# Adafruit_Hallowing_M0_Express.net
KiCad netlist of a schematic drawn in EAGLE
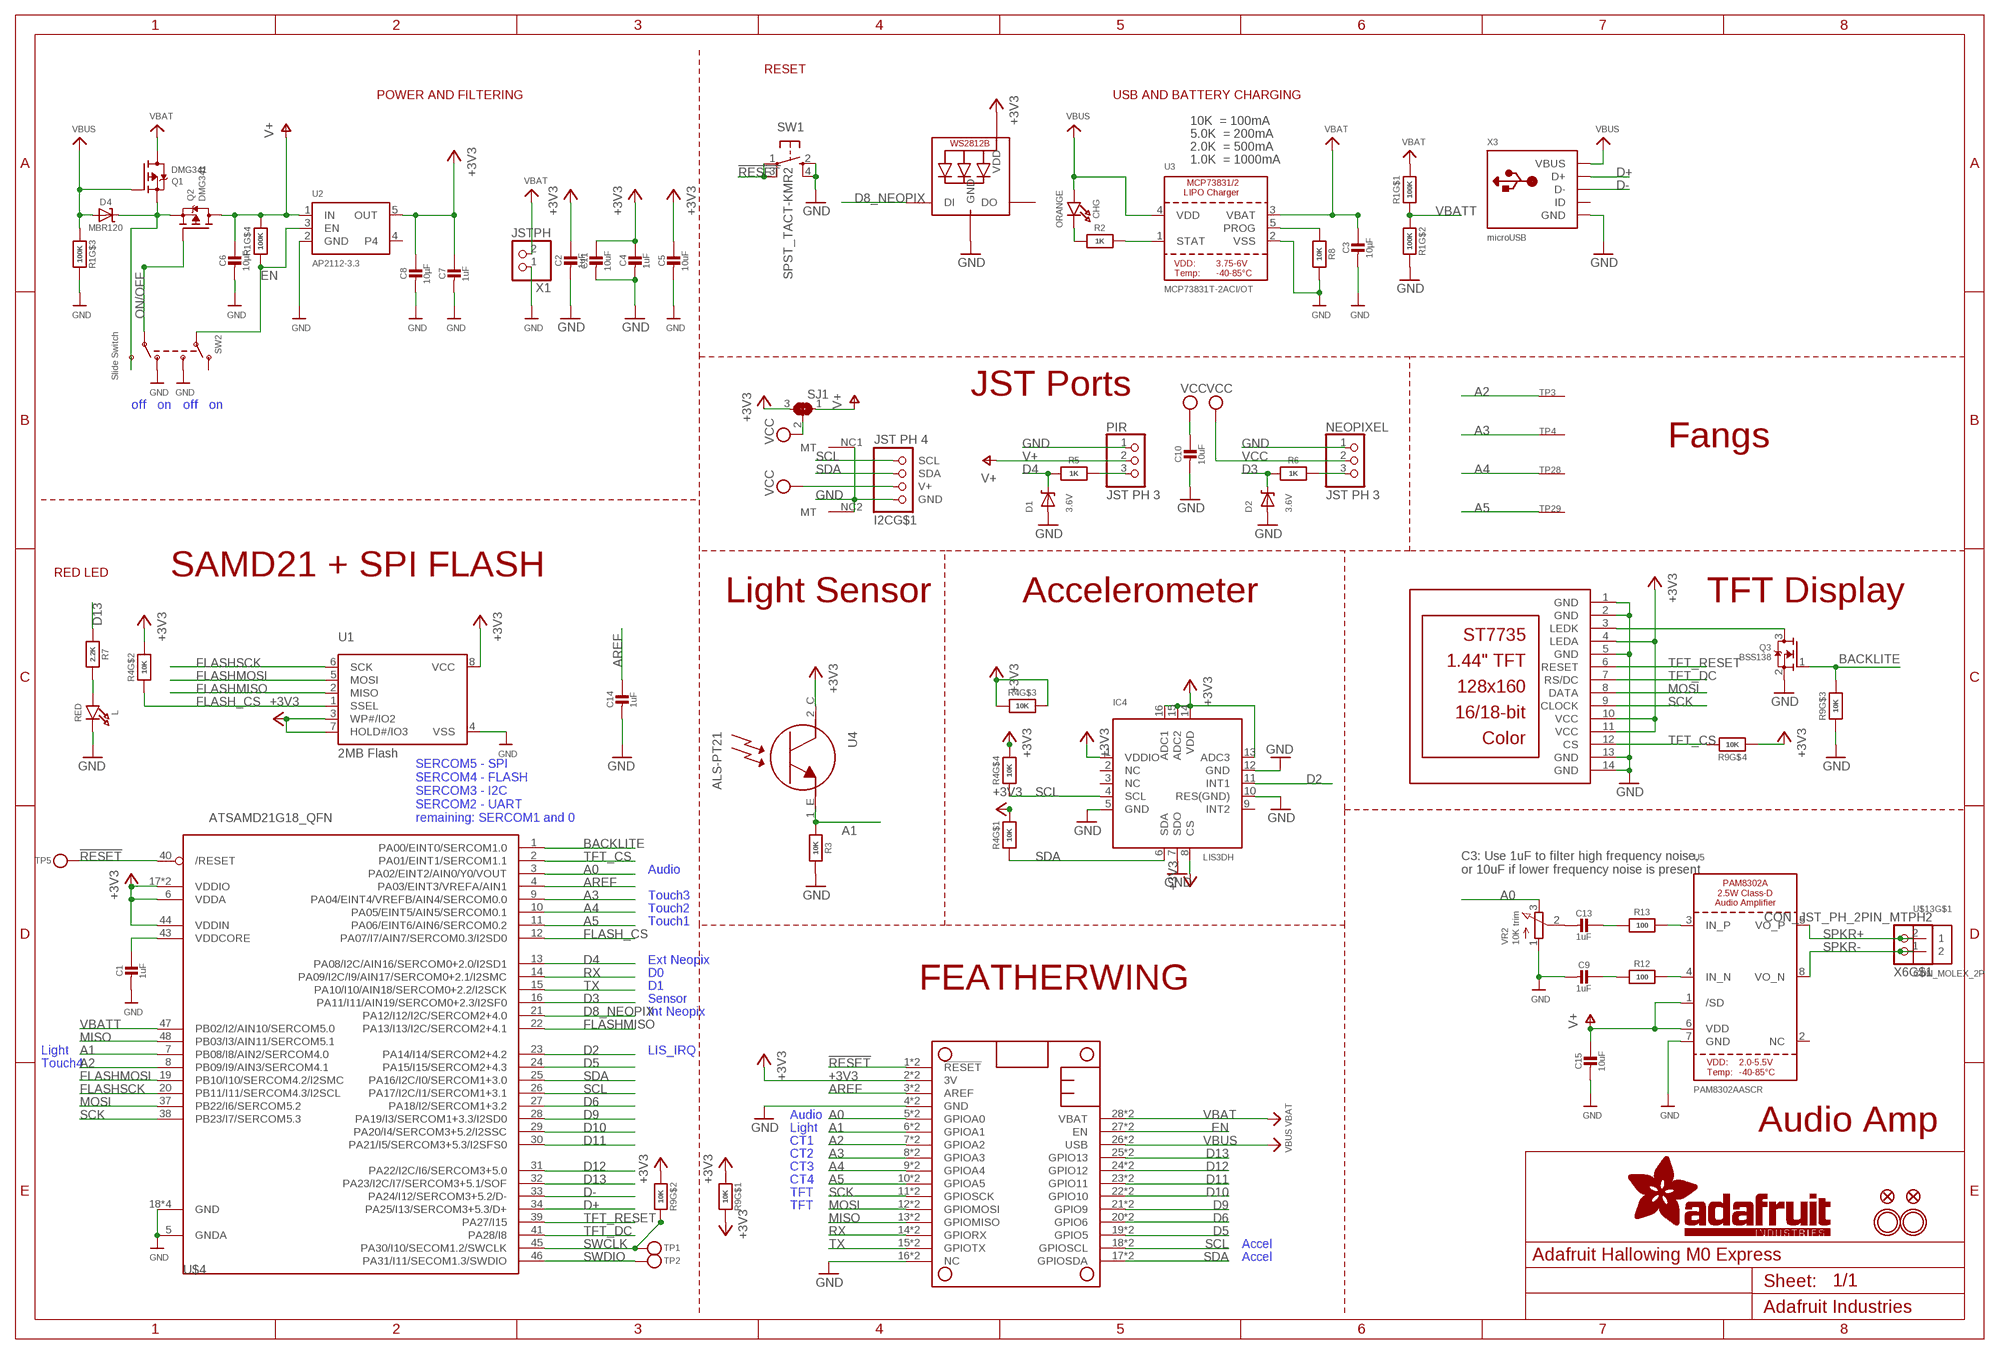
[diagram p0: schematic, sheet 1]

(export (version "E")
  (design (tool "Eeschema 10.0.6"))
  (components
    (comp (ref "C1")
      (value "1uF")
      (footprint "eagle-import:0603-NO")
      (libsource (lib "eagle-import") (part "CAP_CERAMIC0603_NO"))
    )
    (comp (ref "C2")
      (value "1uF")
      (footprint "eagle-import:0603-NO")
      (libsource (lib "eagle-import") (part "CAP_CERAMIC0603_NO"))
    )
    (comp (ref "C3")
      (value "10µF")
      (footprint "eagle-import:0805-NO")
      (libsource (lib "eagle-import") (part "CAP_CERAMIC0805-NOOUTLINE"))
    )
    (comp (ref "C4")
      (value "1uF")
      (footprint "eagle-import:0603-NO")
      (libsource (lib "eagle-import") (part "CAP_CERAMIC0603_NO"))
    )
    (comp (ref "C5")
      (value "10uF")
      (footprint "eagle-import:0805-NO")
      (libsource (lib "eagle-import") (part "CAP_CERAMIC0805-NOOUTLINE"))
    )
    (comp (ref "C6")
      (value "10µF")
      (footprint "eagle-import:0805-NO")
      (libsource (lib "eagle-import") (part "CAP_CERAMIC0805-NOOUTLINE"))
    )
    (comp (ref "C7")
      (value "1uF")
      (footprint "eagle-import:0603-NO")
      (libsource (lib "eagle-import") (part "CAP_CERAMIC0603_NO"))
    )
    (comp (ref "C8")
      (value "10µF")
      (footprint "eagle-import:0805_10MGAP")
      (libsource (lib "eagle-import") (part "CAP_CERAMIC0805_10MGAP"))
    )
    (comp (ref "C9")
      (value "1uF")
      (footprint "eagle-import:0603-NO")
      (libsource (lib "eagle-import") (part "CAP_CERAMIC0603_NO"))
    )
    (comp (ref "C10")
      (value "10uF")
      (footprint "eagle-import:0805-NO")
      (libsource (lib "eagle-import") (part "CAP_CERAMIC0805-NOOUTLINE"))
    )
    (comp (ref "C11")
      (value "10uF")
      (footprint "eagle-import:0805_10MGAP")
      (libsource (lib "eagle-import") (part "CAP_CERAMIC0805_10MGAP"))
    )
    (comp (ref "C13")
      (value "1uF")
      (footprint "eagle-import:0603-NO")
      (libsource (lib "eagle-import") (part "CAP_CERAMIC0603_NO"))
    )
    (comp (ref "C14")
      (value "1uF")
      (footprint "eagle-import:0603-NO")
      (libsource (lib "eagle-import") (part "CAP_CERAMIC0603_NO"))
    )
    (comp (ref "C15")
      (value "10uF")
      (footprint "eagle-import:0805-NO")
      (libsource (lib "eagle-import") (part "CAP_CERAMIC0805-NOOUTLINE"))
    )
    (comp (ref "CHG")
      (value "ORANGE")
      (footprint "eagle-import:CHIPLED_0805_NOOUTLINE")
      (libsource (lib "eagle-import") (part "LED0805_NOOUTLINE"))
    )
    (comp (ref "D1")
      (value "3.6V")
      (footprint "eagle-import:SOD-323")
      (libsource (lib "eagle-import") (part "DIODE-ZENERSOD323"))
    )
    (comp (ref "D2")
      (value "3.6V")
      (footprint "eagle-import:SOD-323")
      (libsource (lib "eagle-import") (part "DIODE-ZENERSOD323"))
    )
    (comp (ref "D4")
      (value "MBR120")
      (footprint "eagle-import:SOD-123")
      (libsource (lib "eagle-import") (part "DIODE-SCHOTTKYSOD-123"))
    )
    (comp (ref "I2C")
      (value "JST PH 4")
      (footprint "eagle-import:JSTPH4")
      (libsource (lib "eagle-import") (part "STEMMA_I2C_RASMT"))
    )
    (comp (ref "IC4")
      (value "LIS3DH")
      (footprint "eagle-import:LGA16_3X3MM")
      (libsource (lib "eagle-import") (part "ACCEL_LIS3DHTR"))
    )
    (comp (ref "L")
      (value "RED")
      (footprint "eagle-import:CHIPLED_0805_NOOUTLINE")
      (libsource (lib "eagle-import") (part "LED0805_NOOUTLINE"))
    )
    (comp (ref "LED1")
      (value "WS2812B3535")
      (footprint "eagle-import:LED3535")
      (libsource (lib "eagle-import") (part "WS2812B3535"))
    )
    (comp (ref "MS1")
      (value "FEATHERWING_SMTDUALNOHOLES")
      (footprint "eagle-import:FEATHERWING_SMT_NOHOLES")
      (libsource (lib "eagle-import") (part "FEATHERWING_SMTDUALNOHOLES"))
    )
    (comp (ref "NEOPIXEL")
      (value "JST PH 3")
      (footprint "eagle-import:JSTPH3")
      (libsource (lib "eagle-import") (part "CON_JST_PH_3PIN"))
    )
    (comp (ref "PIR")
      (value "JST PH 3")
      (footprint "eagle-import:JSTPH3")
      (libsource (lib "eagle-import") (part "CON_JST_PH_3PIN"))
    )
    (comp (ref "Q1")
      (value "DMG341")
      (footprint "eagle-import:SOT23-R")
      (libsource (lib "eagle-import") (part "MOSFET-P"))
    )
    (comp (ref "Q2")
      (value "DMG341")
      (footprint "eagle-import:SOT23-R")
      (libsource (lib "eagle-import") (part "MOSFET-P"))
    )
    (comp (ref "Q3")
      (value "BSS138")
      (footprint "eagle-import:SOT23-WIDE")
      (libsource (lib "eagle-import") (part "MOSFET-NWIDE"))
    )
    (comp (ref "R1")
      (value "100K")
      (footprint "eagle-import:RESPACK_4X0603")
      (libsource (lib "eagle-import") (part "RESISTOR_4PACK"))
    )
    (comp (ref "R2")
      (value "1K")
      (footprint "eagle-import:0603-NO")
      (libsource (lib "eagle-import") (part "RESISTOR_0603_NOOUT"))
    )
    (comp (ref "R3")
      (value "10K")
      (footprint "eagle-import:0603-NO")
      (libsource (lib "eagle-import") (part "RESISTOR_0603_NOOUT"))
    )
    (comp (ref "R4")
      (value "10K")
      (footprint "eagle-import:RESPACK_4X0603")
      (libsource (lib "eagle-import") (part "RESISTOR_4PACK"))
    )
    (comp (ref "R5")
      (value "1K")
      (footprint "eagle-import:0603-NO")
      (libsource (lib "eagle-import") (part "RESISTOR_0603_NOOUT"))
    )
    (comp (ref "R6")
      (value "1K")
      (footprint "eagle-import:0603-NO")
      (libsource (lib "eagle-import") (part "RESISTOR_0603_NOOUT"))
    )
    (comp (ref "R7")
      (value "2.2K")
      (footprint "eagle-import:0603-NO")
      (libsource (lib "eagle-import") (part "RESISTOR_0603_NOOUT"))
    )
    (comp (ref "R8")
      (value "10K")
      (footprint "eagle-import:0603-NO")
      (libsource (lib "eagle-import") (part "RESISTOR_0603_NOOUT"))
    )
    (comp (ref "R9")
      (value "10K")
      (footprint "eagle-import:RESPACK_4X0603")
      (libsource (lib "eagle-import") (part "RESISTOR_4PACK"))
    )
    (comp (ref "R12")
      (value "100")
      (footprint "eagle-import:0603-NO")
      (libsource (lib "eagle-import") (part "RESISTOR_0603_NOOUT"))
    )
    (comp (ref "R13")
      (value "100")
      (footprint "eagle-import:0603-NO")
      (libsource (lib "eagle-import") (part "RESISTOR_0603_NOOUT"))
    )
    (comp (ref "SJ1")
      (value "SOLDERJUMPER_2WAY")
      (footprint "eagle-import:SOLDERJUMPER_2WAY_OPEN_NOPASTE")
      (libsource (lib "eagle-import") (part "SOLDERJUMPER_2WAY"))
    )
    (comp (ref "SW1")
      (value "SPST_TACT-KMR2")
      (footprint "eagle-import:KMR2")
      (libsource (lib "eagle-import") (part "SPST_TACT-KMR2"))
    )
    (comp (ref "SW2")
      (value "Slide Switch")
      (footprint "eagle-import:EG1390")
      (libsource (lib "eagle-import") (part "SWITCH_DPDTEG1390"))
    )
    (comp (ref "TFT")
      (value "DISP_LCD_ST7735_1.44IN")
      (footprint "eagle-import:TFT_1.44IN_128_128")
      (libsource (lib "eagle-import") (part "DISP_LCD_ST7735_1.44IN"))
    )
    (comp (ref "TP1")
      (value "TESTPOINTROUND1.5MM")
      (footprint "eagle-import:TESTPOINT_ROUND_1.5MM")
      (libsource (lib "eagle-import") (part "TESTPOINTROUND1.5MM"))
    )
    (comp (ref "TP2")
      (value "TESTPOINTROUND1.5MM")
      (footprint "eagle-import:TESTPOINT_ROUND_1.5MM")
      (libsource (lib "eagle-import") (part "TESTPOINTROUND1.5MM"))
    )
    (comp (ref "TP3")
      (value "SEWTAP_ALLILONG")
      (footprint "eagle-import:PCB_ALLI_LONG")
      (libsource (lib "eagle-import") (part "SEWTAP_ALLILONG"))
    )
    (comp (ref "TP4")
      (value "SEWTAPPCB_ALLIGATOR")
      (footprint "eagle-import:PCB_ALLI")
      (libsource (lib "eagle-import") (part "SEWTAPPCB_ALLIGATOR"))
    )
    (comp (ref "TP5")
      (value "TESTPOINTROUND1.5MM")
      (footprint "eagle-import:TESTPOINT_ROUND_1.5MM")
      (libsource (lib "eagle-import") (part "TESTPOINTROUND1.5MM"))
    )
    (comp (ref "TP28")
      (value "SEWTAPPCB_ALLIGATOR")
      (footprint "eagle-import:PCB_ALLI")
      (libsource (lib "eagle-import") (part "SEWTAPPCB_ALLIGATOR"))
    )
    (comp (ref "TP29")
      (value "SEWTAP_ALLILONG")
      (footprint "eagle-import:PCB_ALLI_LONG")
      (libsource (lib "eagle-import") (part "SEWTAP_ALLILONG"))
    )
    (comp (ref "U$4")
      (value "ATSAMD21G18_QFN")
      (footprint "eagle-import:TQFN48_7MM")
      (libsource (lib "eagle-import") (part "ATSAMD21G_QFN"))
    )
    (comp (ref "U$13")
      (value "CON_MOLEX_2P")
      (footprint "eagle-import:53398-0271")
      (libsource (lib "eagle-import") (part "CON_MOLEX_2P"))
    )
    (comp (ref "U$31")
      (value "MOUNTINGHOLE2.5")
      (footprint "eagle-import:MOUNTINGHOLE_2.5_PLATED")
      (libsource (lib "eagle-import") (part "MOUNTINGHOLE2.5"))
    )
    (comp (ref "U$32")
      (value "MOUNTINGHOLE2.5")
      (footprint "eagle-import:MOUNTINGHOLE_2.5_PLATED")
      (libsource (lib "eagle-import") (part "MOUNTINGHOLE2.5"))
    )
    (comp (ref "U$34")
      (value "FIDUCIAL_1MM")
      (footprint "eagle-import:FIDUCIAL_1MM")
      (libsource (lib "eagle-import") (part "FIDUCIAL_1MM"))
    )
    (comp (ref "U$35")
      (value "FIDUCIAL_1MM")
      (footprint "eagle-import:FIDUCIAL_1MM")
      (libsource (lib "eagle-import") (part "FIDUCIAL_1MM"))
    )
    (comp (ref "U1")
      (value "2MB Flash")
      (footprint "eagle-import:SOIC8_208MIL")
      (libsource (lib "eagle-import") (part "SPIFLASH_8PIN208MIL"))
    )
    (comp (ref "U2")
      (value "AP2112-3.3")
      (footprint "eagle-import:SOT23-5")
      (libsource (lib "eagle-import") (part "VREG_SOT23-5"))
    )
    (comp (ref "U3")
      (value "MCP73831T-2ACI/OT")
      (footprint "eagle-import:SOT23-5")
      (libsource (lib "eagle-import") (part "MCP73831/2"))
    )
    (comp (ref "U4")
      (value "ALS-PT21")
      (footprint "eagle-import:ALS-PT26-21C")
      (libsource (lib "eagle-import") (part "PHOTOTRANSISTOR_PT26-21C"))
    )
    (comp (ref "U5")
      (value "PAM8302AASCR")
      (footprint "eagle-import:MSOP8_0.65MM")
      (libsource (lib "eagle-import") (part "AUDIOAMP_PAM8302A"))
    )
    (comp (ref "VR2")
      (value "10K trim")
      (footprint "eagle-import:TRIMPOT_BOURNS_3303W")
      (libsource (lib "eagle-import") (part "TRIMPOT3303W/X"))
    )
    (comp (ref "X1")
      (value "JSTPH")
      (footprint "eagle-import:JSTPH2")
      (libsource (lib "eagle-import") (part "CON_JST_PH_2PIN"))
    )
    (comp (ref "X3")
      (value "microUSB")
      (footprint "eagle-import:4UCONN_20329_V2")
      (libsource (lib "eagle-import") (part "USB_MICRO_20329_V2"))
    )
    (comp (ref "X6")
      (value "CON_JST_PH_2PIN_MTPH2")
      (footprint "eagle-import:JSTPH2")
      (libsource (lib "eagle-import") (part "CON_JST_PH_2PIN_MTPH2"))
    )
  )
  (nets
    (net (code "1") (name "+3V3") (class "Default")
      (node (ref "C11") (pin "1") (pinfunction "1_1") (pintype "passive"))
      (node (ref "C2") (pin "1") (pinfunction "1_1") (pintype "passive"))
      (node (ref "C4") (pin "1") (pinfunction "1_1") (pintype "passive"))
      (node (ref "C5") (pin "1") (pinfunction "1_1") (pintype "passive"))
      (node (ref "C7") (pin "1") (pinfunction "1_1") (pintype "passive"))
      (node (ref "C8") (pin "1") (pinfunction "1_1") (pintype "passive"))
      (node (ref "IC4") (pin "1") (pinfunction "VDDIO_1") (pintype "power_in"))
      (node (ref "IC4") (pin "13") (pinfunction "ADC3_13") (pintype "input"))
      (node (ref "IC4") (pin "14") (pinfunction "VDD_14") (pintype "power_in"))
      (node (ref "IC4") (pin "15") (pinfunction "ADC2_15") (pintype "input"))
      (node (ref "IC4") (pin "16") (pinfunction "ADC1_16") (pintype "input"))
      (node (ref "IC4") (pin "8") (pinfunction "CS_8") (pintype "input"))
      (node (ref "LED1") (pin "2") (pinfunction "VDD_2") (pintype "power_in"))
      (node (ref "MS1") (pin "2") (pinfunction "3V_2") (pintype "power_in"))
      (node (ref "MS1") (pin "2'") (pinfunction "3V_2'") (pintype "power_in"))
      (node (ref "R4") (pin "3") (pinfunction "1_3") (pintype "passive"))
      (node (ref "R4") (pin "5") (pinfunction "2_5") (pintype "passive"))
      (node (ref "R4") (pin "6") (pinfunction "2_6") (pintype "passive"))
      (node (ref "R4") (pin "7") (pinfunction "2_7") (pintype "passive"))
      (node (ref "R4") (pin "8") (pinfunction "2_8") (pintype "passive"))
      (node (ref "R9") (pin "1") (pinfunction "1_1") (pintype "passive"))
      (node (ref "R9") (pin "2") (pinfunction "1_2") (pintype "passive"))
      (node (ref "R9") (pin "4") (pinfunction "1_4") (pintype "passive"))
      (node (ref "R9") (pin "8") (pinfunction "2_8") (pintype "passive"))
      (node (ref "SJ1") (pin "3") (pinfunction "3_3") (pintype "passive"))
      (node (ref "TFT") (pin "10") (pinfunction "VCC_10") (pintype "power_in"))
      (node (ref "TFT") (pin "11") (pinfunction "VCC_11") (pintype "power_in"))
      (node (ref "TFT") (pin "4") (pinfunction "LEDA_4") (pintype "input"))
      (node (ref "U$4") (pin "17") (pinfunction "VDDIO_17") (pintype "power_in"))
      (node (ref "U$4") (pin "36") (pinfunction "VDDIO_36") (pintype "power_in"))
      (node (ref "U$4") (pin "44") (pinfunction "VDDIN_44") (pintype "power_in"))
      (node (ref "U$4") (pin "6") (pinfunction "VDDA_6") (pintype "power_in"))
      (node (ref "U1") (pin "3") (pinfunction "WP#/IO2_3") (pintype "bidirectional"))
      (node (ref "U1") (pin "7") (pinfunction "HOLD#/IO3_7") (pintype "bidirectional"))
      (node (ref "U1") (pin "8") (pinfunction "VCC_8") (pintype "bidirectional"))
      (node (ref "U2") (pin "5") (pinfunction "OUT_5") (pintype "power_in"))
      (node (ref "U4") (pin "2_C") (pinfunction "C_2_C") (pintype "bidirectional"))
    )
    (net (code "2") (name "/A0") (class "Default")
      (node (ref "MS1") (pin "5") (pinfunction "GPIOA0_5") (pintype "bidirectional"))
      (node (ref "MS1") (pin "5'") (pinfunction "GPIOA0_5'") (pintype "bidirectional"))
      (node (ref "U$4") (pin "3") (pinfunction "PA02/EINT2/AIN0/Y0/VOUT_3") (pintype "bidirectional"))
      (node (ref "VR2") (pin "3") (pinfunction "E_3") (pintype "passive"))
    )
    (net (code "3") (name "/A1") (class "Default")
      (node (ref "MS1") (pin "6") (pinfunction "GPIOA1_6") (pintype "bidirectional"))
      (node (ref "MS1") (pin "6'") (pinfunction "GPIOA1_6'") (pintype "bidirectional"))
      (node (ref "R3") (pin "2") (pinfunction "2_2") (pintype "passive"))
      (node (ref "U$4") (pin "7") (pinfunction "PB08/I8/AIN2/SERCOM4.0_7") (pintype "bidirectional"))
      (node (ref "U4") (pin "1_E") (pinfunction "E_1_E") (pintype "bidirectional"))
    )
    (net (code "4") (name "/A2") (class "Default")
      (node (ref "MS1") (pin "7") (pinfunction "GPIOA2_7") (pintype "bidirectional"))
      (node (ref "MS1") (pin "7'") (pinfunction "GPIOA2_7'") (pintype "bidirectional"))
      (node (ref "TP3") (pin "P$1") (pinfunction "SEW_P$1") (pintype "bidirectional"))
      (node (ref "U$4") (pin "8") (pinfunction "PB09/I9/AIN3/SERCOM4.1_8") (pintype "bidirectional"))
    )
    (net (code "5") (name "/A3") (class "Default")
      (node (ref "MS1") (pin "8") (pinfunction "GPIOA3_8") (pintype "bidirectional"))
      (node (ref "MS1") (pin "8'") (pinfunction "GPIOA3_8'") (pintype "bidirectional"))
      (node (ref "TP4") (pin "P$1") (pinfunction "SEW_P$1") (pintype "bidirectional"))
      (node (ref "U$4") (pin "9") (pinfunction "PA04/EINT4/VREFB/AIN4/SERCOM0.0_9") (pintype "bidirectional"))
    )
    (net (code "6") (name "/A4") (class "Default")
      (node (ref "MS1") (pin "9") (pinfunction "GPIOA4_9") (pintype "bidirectional"))
      (node (ref "MS1") (pin "9'") (pinfunction "GPIOA4_9'") (pintype "bidirectional"))
      (node (ref "TP28") (pin "P$1") (pinfunction "SEW_P$1") (pintype "bidirectional"))
      (node (ref "U$4") (pin "10") (pinfunction "PA05/EINT5/AIN5/SERCOM0.1_10") (pintype "bidirectional"))
    )
    (net (code "7") (name "/A5") (class "Default")
      (node (ref "MS1") (pin "10") (pinfunction "GPIOA5_10") (pintype "bidirectional"))
      (node (ref "MS1") (pin "10'") (pinfunction "GPIOA5_10'") (pintype "bidirectional"))
      (node (ref "TP29") (pin "P$1") (pinfunction "SEW_P$1") (pintype "bidirectional"))
      (node (ref "U$4") (pin "11") (pinfunction "PA06/EINT6/AIN6/SERCOM0.2_11") (pintype "bidirectional"))
    )
    (net (code "8") (name "/AREF") (class "Default")
      (node (ref "C14") (pin "1") (pinfunction "1_1") (pintype "passive"))
      (node (ref "MS1") (pin "3") (pinfunction "AREF_3") (pintype "passive"))
      (node (ref "MS1") (pin "3'") (pinfunction "AREF_3'") (pintype "passive"))
      (node (ref "U$4") (pin "4") (pinfunction "PA03/EINT3/VREFA/AIN1_4") (pintype "bidirectional"))
    )
    (net (code "9") (name "/BACKLITE") (class "Default")
      (node (ref "Q3") (pin "1") (pinfunction "G_1") (pintype "bidirectional"))
      (node (ref "R9") (pin "6") (pinfunction "2_6") (pintype "passive"))
      (node (ref "U$4") (pin "1") (pinfunction "PA00/EINT0/SERCOM1.0_1") (pintype "bidirectional"))
    )
    (net (code "10") (name "/D+") (class "Default")
      (node (ref "U$4") (pin "34") (pinfunction "PA25/I13/SERCOM3+5.3/D+_34") (pintype "bidirectional"))
      (node (ref "X3") (pin "D+") (pinfunction "D+_D+") (pintype "bidirectional"))
    )
    (net (code "11") (name "/D-") (class "Default")
      (node (ref "U$4") (pin "33") (pinfunction "PA24/I12/SERCOM3+5.2/D-_33") (pintype "bidirectional"))
      (node (ref "X3") (pin "D-") (pinfunction "D-_D-") (pintype "bidirectional"))
    )
    (net (code "12") (name "/D2") (class "Default")
      (node (ref "IC4") (pin "11") (pinfunction "INT1_11") (pintype "output"))
      (node (ref "U$4") (pin "23") (pinfunction "PA14/I14/SERCOM2+4.2_23") (pintype "bidirectional"))
    )
    (net (code "13") (name "/D3") (class "Default")
      (node (ref "D2") (pin "C") (pinfunction "C_C") (pintype "passive"))
      (node (ref "R6") (pin "2") (pinfunction "2_2") (pintype "passive"))
      (node (ref "U$4") (pin "16") (pinfunction "PA11/I11/AIN19/SERCOM0+2.3/I2SF0_16") (pintype "bidirectional"))
    )
    (net (code "14") (name "/D4") (class "Default")
      (node (ref "D1") (pin "C") (pinfunction "C_C") (pintype "passive"))
      (node (ref "R5") (pin "2") (pinfunction "2_2") (pintype "passive"))
      (node (ref "U$4") (pin "13") (pinfunction "PA08/I2C/AIN16/SERCOM0+2.0/I2SD1_13") (pintype "bidirectional"))
    )
    (net (code "15") (name "/D5") (class "Default")
      (node (ref "MS1") (pin "19") (pinfunction "GPIO5_19") (pintype "bidirectional"))
      (node (ref "MS1") (pin "19'") (pinfunction "GPIO5_19'") (pintype "bidirectional"))
      (node (ref "U$4") (pin "24") (pinfunction "PA15/I15/SERCOM2+4.3_24") (pintype "bidirectional"))
    )
    (net (code "16") (name "/D6") (class "Default")
      (node (ref "MS1") (pin "20") (pinfunction "GPIO6_20") (pintype "bidirectional"))
      (node (ref "MS1") (pin "20'") (pinfunction "GPIO6_20'") (pintype "bidirectional"))
      (node (ref "U$4") (pin "27") (pinfunction "PA18/I2/SERCOM1+3.2_27") (pintype "bidirectional"))
    )
    (net (code "17") (name "/D8_NEOPIX") (class "Default")
      (node (ref "LED1") (pin "1") (pinfunction "DI_1") (pintype "input"))
      (node (ref "U$4") (pin "21") (pinfunction "PA12/I12/I2C/SERCOM2+4.0_21") (pintype "bidirectional"))
    )
    (net (code "18") (name "/D9") (class "Default")
      (node (ref "MS1") (pin "21") (pinfunction "GPIO9_21") (pintype "bidirectional"))
      (node (ref "MS1") (pin "21'") (pinfunction "GPIO9_21'") (pintype "bidirectional"))
      (node (ref "U$4") (pin "28") (pinfunction "PA19/I3/SERCOM1+3.3/I2SD0_28") (pintype "bidirectional"))
    )
    (net (code "19") (name "/D10") (class "Default")
      (node (ref "MS1") (pin "22") (pinfunction "GPIO10_22") (pintype "bidirectional"))
      (node (ref "MS1") (pin "22'") (pinfunction "GPIO10_22'") (pintype "bidirectional"))
      (node (ref "U$4") (pin "29") (pinfunction "PA20/I4/SERCOM3+5.2/I2SSC_29") (pintype "bidirectional"))
    )
    (net (code "20") (name "/D11") (class "Default")
      (node (ref "MS1") (pin "23") (pinfunction "GPIO11_23") (pintype "bidirectional"))
      (node (ref "MS1") (pin "23'") (pinfunction "GPIO11_23'") (pintype "bidirectional"))
      (node (ref "U$4") (pin "30") (pinfunction "PA21/I5/SERCOM3+5.3/I2SFS0_30") (pintype "bidirectional"))
    )
    (net (code "21") (name "/D12") (class "Default")
      (node (ref "MS1") (pin "24") (pinfunction "GPIO12_24") (pintype "bidirectional"))
      (node (ref "MS1") (pin "24'") (pinfunction "GPIO12_24'") (pintype "bidirectional"))
      (node (ref "U$4") (pin "31") (pinfunction "PA22/I2C/I6/SERCOM3+5.0_31") (pintype "bidirectional"))
    )
    (net (code "22") (name "/D13") (class "Default")
      (node (ref "MS1") (pin "25") (pinfunction "GPIO13_25") (pintype "bidirectional"))
      (node (ref "MS1") (pin "25'") (pinfunction "GPIO13_25'") (pintype "bidirectional"))
      (node (ref "R7") (pin "1") (pinfunction "1_1") (pintype "passive"))
      (node (ref "U$4") (pin "32") (pinfunction "PA23/I2C/I7/SERCOM3+5.1/SOF_32") (pintype "bidirectional"))
    )
    (net (code "23") (name "/EN") (class "Default")
      (node (ref "MS1") (pin "27") (pinfunction "EN_27") (pintype "passive"))
      (node (ref "MS1") (pin "27'") (pinfunction "EN_27'") (pintype "passive"))
      (node (ref "R1") (pin "4") (pinfunction "1_4") (pintype "passive"))
      (node (ref "SW2") (pin "P1") (pinfunction "P1_P1") (pintype "passive"))
      (node (ref "U2") (pin "3") (pinfunction "EN_3") (pintype "input"))
    )
    (net (code "24") (name "/FLASHMISO") (class "Default")
      (node (ref "U$4") (pin "22") (pinfunction "PA13/I13/I2C/SERCOM2+4.1_22") (pintype "bidirectional"))
      (node (ref "U1") (pin "2") (pinfunction "MISO_2") (pintype "bidirectional"))
    )
    (net (code "25") (name "/FLASHMOSI") (class "Default")
      (node (ref "U$4") (pin "19") (pinfunction "PB10/I10/SERCOM4.2/I2SMC_19") (pintype "bidirectional"))
      (node (ref "U1") (pin "5") (pinfunction "MOSI_5") (pintype "bidirectional"))
    )
    (net (code "26") (name "/FLASHSCK") (class "Default")
      (node (ref "U$4") (pin "20") (pinfunction "PB11/I11/SERCOM4.3/I2SCL_20") (pintype "bidirectional"))
      (node (ref "U1") (pin "6") (pinfunction "SCK_6") (pintype "bidirectional"))
    )
    (net (code "27") (name "/FLASH_CS") (class "Default")
      (node (ref "R4") (pin "2") (pinfunction "1_2") (pintype "passive"))
      (node (ref "U$4") (pin "12") (pinfunction "PA07/I7/AIN7/SERCOM0.3/I2SD0_12") (pintype "bidirectional"))
      (node (ref "U1") (pin "1") (pinfunction "SSEL_1") (pintype "bidirectional"))
    )
    (net (code "28") (name "/MISO") (class "Default")
      (node (ref "MS1") (pin "13") (pinfunction "GPIOMISO_13") (pintype "bidirectional"))
      (node (ref "MS1") (pin "13'") (pinfunction "GPIOMISO_13'") (pintype "bidirectional"))
      (node (ref "U$4") (pin "48") (pinfunction "PB03/I3/AIN11/SERCOM5.1_48") (pintype "bidirectional"))
    )
    (net (code "29") (name "/MOSI") (class "Default")
      (node (ref "MS1") (pin "12") (pinfunction "GPIOMOSI_12") (pintype "bidirectional"))
      (node (ref "MS1") (pin "12'") (pinfunction "GPIOMOSI_12'") (pintype "bidirectional"))
      (node (ref "TFT") (pin "8") (pinfunction "DATA_8") (pintype "bidirectional"))
      (node (ref "U$4") (pin "37") (pinfunction "PB22/I6/SERCOM5.2_37") (pintype "bidirectional"))
    )
    (net (code "30") (name "/ON{slash}OFF") (class "Default")
      (node (ref "Q2") (pin "1") (pinfunction "G_1") (pintype "passive"))
      (node (ref "SW2") (pin "P2") (pinfunction "P2_P2") (pintype "passive"))
    )
    (net (code "31") (name "/RX") (class "Default")
      (node (ref "MS1") (pin "14") (pinfunction "GPIORX_14") (pintype "bidirectional"))
      (node (ref "MS1") (pin "14'") (pinfunction "GPIORX_14'") (pintype "bidirectional"))
      (node (ref "U$4") (pin "14") (pinfunction "PA09/I2C/I9/AIN17/SERCOM0+2.1/I2SMC_14") (pintype "bidirectional"))
    )
    (net (code "32") (name "/SCK") (class "Default")
      (node (ref "MS1") (pin "11") (pinfunction "GPIOSCK_11") (pintype "bidirectional"))
      (node (ref "MS1") (pin "11'") (pinfunction "GPIOSCK_11'") (pintype "bidirectional"))
      (node (ref "TFT") (pin "9") (pinfunction "CLOCK_9") (pintype "input"))
      (node (ref "U$4") (pin "38") (pinfunction "PB23/I7/SERCOM5.3_38") (pintype "bidirectional"))
    )
    (net (code "33") (name "/SCL") (class "Default")
      (node (ref "I2C") (pin "4") (pinfunction "SCL_4") (pintype "passive"))
      (node (ref "IC4") (pin "4") (pinfunction "SCL_4") (pintype "bidirectional"))
      (node (ref "MS1") (pin "18") (pinfunction "GPIOSCL_18") (pintype "bidirectional"))
      (node (ref "MS1") (pin "18'") (pinfunction "GPIOSCL_18'") (pintype "bidirectional"))
      (node (ref "R4") (pin "4") (pinfunction "1_4") (pintype "passive"))
      (node (ref "U$4") (pin "26") (pinfunction "PA17/I2C/I1/SERCOM1+3.1_26") (pintype "bidirectional"))
    )
    (net (code "34") (name "/SDA") (class "Default")
      (node (ref "I2C") (pin "3") (pinfunction "SDA_3") (pintype "passive"))
      (node (ref "IC4") (pin "6") (pinfunction "SDA_6") (pintype "bidirectional"))
      (node (ref "MS1") (pin "17") (pinfunction "GPIOSDA_17") (pintype "bidirectional"))
      (node (ref "MS1") (pin "17'") (pinfunction "GPIOSDA_17'") (pintype "bidirectional"))
      (node (ref "R4") (pin "1") (pinfunction "1_1") (pintype "passive"))
      (node (ref "U$4") (pin "25") (pinfunction "PA16/I2C/I0/SERCOM1+3.0_25") (pintype "bidirectional"))
    )
    (net (code "35") (name "/SPKR+") (class "Default")
      (node (ref "U$13") (pin "1") (pinfunction "1_1") (pintype "passive"))
      (node (ref "U5") (pin "5") (pinfunction "VO_P_5") (pintype "output"))
      (node (ref "X6") (pin "2") (pinfunction "2_2") (pintype "passive"))
    )
    (net (code "36") (name "/SPKR-") (class "Default")
      (node (ref "U$13") (pin "2") (pinfunction "2_2") (pintype "passive"))
      (node (ref "U5") (pin "8") (pinfunction "VO_N_8") (pintype "output"))
      (node (ref "X6") (pin "1") (pinfunction "1_1") (pintype "passive"))
    )
    (net (code "37") (name "/SWCLK") (class "Default")
      (node (ref "R9") (pin "7") (pinfunction "2_7") (pintype "passive"))
      (node (ref "TP1") (pin "P$1") (pinfunction "P$1_P$1") (pintype "bidirectional"))
      (node (ref "U$4") (pin "45") (pinfunction "PA30/I10/SECOM1.2/SWCLK_45") (pintype "bidirectional"))
    )
    (net (code "38") (name "/SWDIO") (class "Default")
      (node (ref "TP2") (pin "P$1") (pinfunction "P$1_P$1") (pintype "bidirectional"))
      (node (ref "U$4") (pin "46") (pinfunction "PA31/I11/SECOM1.3/SWDIO_46") (pintype "bidirectional"))
    )
    (net (code "39") (name "/TFT_CS") (class "Default")
      (node (ref "R9") (pin "5") (pinfunction "2_5") (pintype "passive"))
      (node (ref "TFT") (pin "12") (pinfunction "CS_12") (pintype "input"))
      (node (ref "U$4") (pin "2") (pinfunction "PA01/EINT1/SERCOM1.1_2") (pintype "bidirectional"))
    )
    (net (code "40") (name "/TFT_DC") (class "Default")
      (node (ref "TFT") (pin "7") (pinfunction "RS/DC_7") (pintype "input"))
      (node (ref "U$4") (pin "41") (pinfunction "PA28/I8_41") (pintype "bidirectional"))
    )
    (net (code "41") (name "/TFT_RESET") (class "Default")
      (node (ref "TFT") (pin "6") (pinfunction "RESET_6") (pintype "input"))
      (node (ref "U$4") (pin "39") (pinfunction "PA27/I15_39") (pintype "bidirectional"))
    )
    (net (code "42") (name "/TX") (class "Default")
      (node (ref "MS1") (pin "15") (pinfunction "GPIOTX_15") (pintype "bidirectional"))
      (node (ref "MS1") (pin "15'") (pinfunction "GPIOTX_15'") (pintype "bidirectional"))
      (node (ref "U$4") (pin "15") (pinfunction "PA10/I10/AIN18/SERCOM0+2.2/I2SCK_15") (pintype "bidirectional"))
    )
    (net (code "43") (name "/VBATT") (class "Default")
      (node (ref "R1") (pin "1") (pinfunction "1_1") (pintype "passive"))
      (node (ref "R1") (pin "2") (pinfunction "1_2") (pintype "passive"))
      (node (ref "U$4") (pin "47") (pinfunction "PB02/I2/AIN10/SERCOM5.0_47") (pintype "bidirectional"))
    )
    (net (code "44") (name "/~{RESET}") (class "Default")
      (node (ref "MS1") (pin "1") (pinfunction "~{RESET}_1") (pintype "input"))
      (node (ref "MS1") (pin "1'") (pinfunction "~{RESET}_1'") (pintype "input"))
      (node (ref "SW1") (pin "1") (pinfunction "P_1") (pintype "passive"))
      (node (ref "SW1") (pin "3") (pinfunction "P1_3") (pintype "passive"))
      (node (ref "TP5") (pin "P$1") (pinfunction "P$1_P$1") (pintype "bidirectional"))
      (node (ref "U$4") (pin "40") (pinfunction "/RESET_40") (pintype "bidirectional"))
    )
    (net (code "45") (name "GND") (class "Default")
      (node (ref "C1") (pin "2") (pinfunction "2_2") (pintype "passive"))
      (node (ref "C10") (pin "2") (pinfunction "2_2") (pintype "passive"))
      (node (ref "C11") (pin "2") (pinfunction "2_2") (pintype "passive"))
      (node (ref "C14") (pin "2") (pinfunction "2_2") (pintype "passive"))
      (node (ref "C15") (pin "2") (pinfunction "2_2") (pintype "passive"))
      (node (ref "C2") (pin "2") (pinfunction "2_2") (pintype "passive"))
      (node (ref "C3") (pin "2") (pinfunction "2_2") (pintype "passive"))
      (node (ref "C4") (pin "2") (pinfunction "2_2") (pintype "passive"))
      (node (ref "C5") (pin "2") (pinfunction "2_2") (pintype "passive"))
      (node (ref "C6") (pin "2") (pinfunction "2_2") (pintype "passive"))
      (node (ref "C7") (pin "2") (pinfunction "2_2") (pintype "passive"))
      (node (ref "C8") (pin "2") (pinfunction "2_2") (pintype "passive"))
      (node (ref "C9") (pin "2") (pinfunction "2_2") (pintype "passive"))
      (node (ref "D1") (pin "A") (pinfunction "A_A") (pintype "passive"))
      (node (ref "D2") (pin "A") (pinfunction "A_A") (pintype "passive"))
      (node (ref "I2C") (pin "1") (pinfunction "GND_1") (pintype "passive"))
      (node (ref "I2C") (pin "NC1") (pinfunction "MT_NC1") (pintype "bidirectional"))
      (node (ref "I2C") (pin "NC2") (pinfunction "MT_NC2") (pintype "bidirectional"))
      (node (ref "IC4") (pin "10") (pinfunction "RES(GND)_10") (pintype "bidirectional"))
      (node (ref "IC4") (pin "12") (pinfunction "GND_12") (pintype "power_in"))
      (node (ref "IC4") (pin "5") (pinfunction "GND_5") (pintype "power_in"))
      (node (ref "IC4") (pin "7") (pinfunction "SDO_7") (pintype "bidirectional"))
      (node (ref "L") (pin "C") (pinfunction "C_C") (pintype "passive"))
      (node (ref "LED1") (pin "4") (pinfunction "GND_4") (pintype "power_in"))
      (node (ref "MS1") (pin "16") (pinfunction "NC_16") (pintype "passive"))
      (node (ref "MS1") (pin "16'") (pinfunction "NC_16'") (pintype "passive"))
      (node (ref "MS1") (pin "4") (pinfunction "GND_4") (pintype "power_in"))
      (node (ref "MS1") (pin "4'") (pinfunction "GND_4'") (pintype "power_in"))
      (node (ref "NEOPIXEL") (pin "1") (pinfunction "1_1") (pintype "passive"))
      (node (ref "PIR") (pin "1") (pinfunction "1_1") (pintype "passive"))
      (node (ref "Q3") (pin "2") (pinfunction "S_2") (pintype "bidirectional"))
      (node (ref "R1") (pin "6") (pinfunction "2_6") (pintype "passive"))
      (node (ref "R1") (pin "7") (pinfunction "2_7") (pintype "passive"))
      (node (ref "R3") (pin "1") (pinfunction "1_1") (pintype "passive"))
      (node (ref "R8") (pin "2") (pinfunction "2_2") (pintype "passive"))
      (node (ref "R9") (pin "3") (pinfunction "1_3") (pintype "passive"))
      (node (ref "SW1") (pin "2") (pinfunction "S_2") (pintype "passive"))
      (node (ref "SW1") (pin "4") (pinfunction "S1_4") (pintype "passive"))
      (node (ref "SW2") (pin "O2") (pinfunction "O2_O2") (pintype "passive"))
      (node (ref "SW2") (pin "S1") (pinfunction "S1_S1") (pintype "passive"))
      (node (ref "TFT") (pin "1") (pinfunction "GND_1") (pintype "power_in"))
      (node (ref "TFT") (pin "13") (pinfunction "GND_13") (pintype "power_in"))
      (node (ref "TFT") (pin "14") (pinfunction "GND_14") (pintype "power_in"))
      (node (ref "TFT") (pin "2") (pinfunction "GND_2") (pintype "power_in"))
      (node (ref "TFT") (pin "5") (pinfunction "GND_5") (pintype "power_in"))
      (node (ref "U$4") (pin "18") (pinfunction "GND_18") (pintype "power_in"))
      (node (ref "U$4") (pin "35") (pinfunction "GND_35") (pintype "power_in"))
      (node (ref "U$4") (pin "42") (pinfunction "GND_42") (pintype "power_in"))
      (node (ref "U$4") (pin "5") (pinfunction "GNDA_5") (pintype "power_in"))
      (node (ref "U$4") (pin "THERMAL") (pinfunction "GND_THERMAL") (pintype "power_in"))
      (node (ref "U1") (pin "4") (pinfunction "VSS_4") (pintype "bidirectional"))
      (node (ref "U2") (pin "2") (pinfunction "GND_2") (pintype "power_in"))
      (node (ref "U3") (pin "2") (pinfunction "VSS_2") (pintype "power_in"))
      (node (ref "U5") (pin "7") (pinfunction "GND_7") (pintype "power_in"))
      (node (ref "VR2") (pin "1") (pinfunction "A_1") (pintype "passive"))
      (node (ref "X1") (pin "1") (pinfunction "1_1") (pintype "passive"))
      (node (ref "X3") (pin "BASE@1") (pinfunction "GND_BASE@1") (pintype "power_in"))
      (node (ref "X3") (pin "BASE@2") (pinfunction "GND_BASE@2") (pintype "power_in"))
      (node (ref "X3") (pin "GND") (pinfunction "GND_GND") (pintype "power_in"))
      (node (ref "X3") (pin "SPRT@1") (pinfunction "GND_SPRT@1") (pintype "power_in"))
      (node (ref "X3") (pin "SPRT@2") (pinfunction "GND_SPRT@2") (pintype "power_in"))
      (node (ref "X3") (pin "SPRT@3") (pinfunction "GND_SPRT@3") (pintype "power_in"))
      (node (ref "X3") (pin "SPRT@4") (pinfunction "GND_SPRT@4") (pintype "power_in"))
    )
    (net (code "46") (name "Net-(C9-Pad1)") (class "Default")
      (node (ref "C9") (pin "1") (pinfunction "1_1") (pintype "passive"))
      (node (ref "R12") (pin "1") (pinfunction "1_1") (pintype "passive"))
    )
    (net (code "47") (name "Net-(C13-Pad1)") (class "Default")
      (node (ref "C13") (pin "1") (pinfunction "1_1") (pintype "passive"))
      (node (ref "R13") (pin "1") (pinfunction "1_1") (pintype "passive"))
    )
    (net (code "48") (name "Net-(CHG-PadC)") (class "Default")
      (node (ref "CHG") (pin "C") (pinfunction "C_C") (pintype "passive"))
      (node (ref "R2") (pin "1") (pinfunction "1_1") (pintype "passive"))
    )
    (net (code "49") (name "Net-(L-PadA)") (class "Default")
      (node (ref "L") (pin "A") (pinfunction "A_A") (pintype "passive"))
      (node (ref "R7") (pin "2") (pinfunction "2_2") (pintype "passive"))
    )
    (net (code "50") (name "Net-(NEOPIXEL-Pad3)") (class "Default")
      (node (ref "NEOPIXEL") (pin "3") (pinfunction "3_3") (pintype "passive"))
      (node (ref "R6") (pin "1") (pinfunction "1_1") (pintype "passive"))
    )
    (net (code "51") (name "Net-(PIR-Pad3)") (class "Default")
      (node (ref "PIR") (pin "3") (pinfunction "3_3") (pintype "passive"))
      (node (ref "R5") (pin "1") (pinfunction "1_1") (pintype "passive"))
    )
    (net (code "52") (name "Net-(Q1-S)") (class "Default")
      (node (ref "D4") (pin "C") (pinfunction "C_C") (pintype "passive"))
      (node (ref "Q1") (pin "2") (pinfunction "S_2") (pintype "passive"))
      (node (ref "Q2") (pin "2") (pinfunction "S_2") (pintype "passive"))
      (node (ref "SW2") (pin "S2") (pinfunction "S2_S2") (pintype "passive"))
    )
    (net (code "53") (name "Net-(Q3-D)") (class "Default")
      (node (ref "Q3") (pin "3") (pinfunction "D_3") (pintype "bidirectional"))
      (node (ref "TFT") (pin "3") (pinfunction "LEDK_3") (pintype "input"))
    )
    (net (code "54") (name "Net-(U$4-VDDCORE)") (class "Default")
      (node (ref "C1") (pin "1") (pinfunction "1_1") (pintype "passive"))
      (node (ref "U$4") (pin "43") (pinfunction "VDDCORE_43") (pintype "power_in"))
    )
    (net (code "55") (name "Net-(U3-PROG)") (class "Default")
      (node (ref "R8") (pin "1") (pinfunction "1_1") (pintype "passive"))
      (node (ref "U3") (pin "5") (pinfunction "PROG_5") (pintype "input"))
    )
    (net (code "56") (name "Net-(U3-STAT)") (class "Default")
      (node (ref "R2") (pin "2") (pinfunction "2_2") (pintype "passive"))
      (node (ref "U3") (pin "1") (pinfunction "STAT_1") (pintype "output"))
    )
    (net (code "57") (name "Net-(U5-IN_N)") (class "Default")
      (node (ref "R12") (pin "2") (pinfunction "2_2") (pintype "passive"))
      (node (ref "U5") (pin "4") (pinfunction "IN_N_4") (pintype "input"))
    )
    (net (code "58") (name "Net-(U5-IN_P)") (class "Default")
      (node (ref "R13") (pin "2") (pinfunction "2_2") (pintype "passive"))
      (node (ref "U5") (pin "3") (pinfunction "IN_P_3") (pintype "input"))
    )
    (net (code "59") (name "Net-(VR2-S)") (class "Default")
      (node (ref "C13") (pin "2") (pinfunction "2_2") (pintype "passive"))
      (node (ref "VR2") (pin "2") (pinfunction "S_2") (pintype "passive"))
    )
    (net (code "60") (name "V+") (class "Default")
      (node (ref "C15") (pin "1") (pinfunction "1_1") (pintype "passive"))
      (node (ref "C6") (pin "1") (pinfunction "1_1") (pintype "passive"))
      (node (ref "PIR") (pin "2") (pinfunction "2_2") (pintype "passive"))
      (node (ref "Q2") (pin "3") (pinfunction "D_3") (pintype "passive"))
      (node (ref "R1") (pin "5") (pinfunction "2_5") (pintype "passive"))
      (node (ref "SJ1") (pin "1") (pinfunction "1_1") (pintype "passive"))
      (node (ref "U2") (pin "1") (pinfunction "IN_1") (pintype "power_in"))
      (node (ref "U5") (pin "1") (pinfunction "/SD_1") (pintype "input"))
      (node (ref "U5") (pin "6") (pinfunction "VDD_6") (pintype "power_in"))
    )
    (net (code "61") (name "VBAT") (class "Default")
      (node (ref "C3") (pin "1") (pinfunction "1_1") (pintype "passive"))
      (node (ref "MS1") (pin "28") (pinfunction "VBAT_28") (pintype "power_in"))
      (node (ref "MS1") (pin "28'") (pinfunction "VBAT_28'") (pintype "power_in"))
      (node (ref "Q1") (pin "3") (pinfunction "D_3") (pintype "passive"))
      (node (ref "R1") (pin "8") (pinfunction "2_8") (pintype "passive"))
      (node (ref "U3") (pin "3") (pinfunction "VBAT_3") (pintype "power_in"))
      (node (ref "X1") (pin "2") (pinfunction "2_2") (pintype "passive"))
    )
    (net (code "62") (name "VBUS") (class "Default")
      (node (ref "CHG") (pin "A") (pinfunction "A_A") (pintype "passive"))
      (node (ref "D4") (pin "A") (pinfunction "A_A") (pintype "passive"))
      (node (ref "MS1") (pin "26") (pinfunction "USB_26") (pintype "power_in"))
      (node (ref "MS1") (pin "26'") (pinfunction "USB_26'") (pintype "power_in"))
      (node (ref "Q1") (pin "1") (pinfunction "G_1") (pintype "passive"))
      (node (ref "R1") (pin "3") (pinfunction "1_3") (pintype "passive"))
      (node (ref "U3") (pin "4") (pinfunction "VDD_4") (pintype "power_in"))
      (node (ref "X3") (pin "VBUS") (pinfunction "VBUS_VBUS") (pintype "power_in"))
    )
    (net (code "63") (name "VCC") (class "Default")
      (node (ref "C10") (pin "1") (pinfunction "1_1") (pintype "passive"))
      (node (ref "I2C") (pin "2") (pinfunction "V+_2") (pintype "passive"))
      (node (ref "NEOPIXEL") (pin "2") (pinfunction "2_2") (pintype "passive"))
      (node (ref "SJ1") (pin "2") (pinfunction "2_2") (pintype "passive"))
    )
    (net (code "64") (name "unconnected-(IC4-INT2-Pad9)") (class "Default")
      (node (ref "IC4") (pin "9") (pinfunction "INT2_9") (pintype "output"))
    )
    (net (code "65") (name "unconnected-(IC4-NC-Pad2)") (class "Default")
      (node (ref "IC4") (pin "2") (pinfunction "NC_2") (pintype "no_connect"))
    )
    (net (code "66") (name "unconnected-(IC4-NC-Pad3)") (class "Default")
      (node (ref "IC4") (pin "3") (pinfunction "NC_3") (pintype "no_connect"))
    )
    (net (code "67") (name "unconnected-(LED1-DO-Pad3)") (class "Default")
      (node (ref "LED1") (pin "3") (pinfunction "DO_3") (pintype "output"))
    )
    (net (code "68") (name "unconnected-(SW2-PadO1)") (class "Default")
      (node (ref "SW2") (pin "O1") (pinfunction "O1_O1") (pintype "passive"))
    )
    (net (code "69") (name "unconnected-(U2-P4-Pad4)") (class "Default")
      (node (ref "U2") (pin "4") (pinfunction "P4_4") (pintype "bidirectional"))
    )
    (net (code "70") (name "unconnected-(U5-NC-Pad2)") (class "Default")
      (node (ref "U5") (pin "2") (pinfunction "NC_2") (pintype "no_connect"))
    )
    (net (code "71") (name "unconnected-(X3-PadID)") (class "Default")
      (node (ref "X3") (pin "ID") (pinfunction "ID_ID") (pintype "bidirectional"))
    )
  )
)
